# RB_Audio.net
KiCad netlist of a schematic drawn in Altium Designer
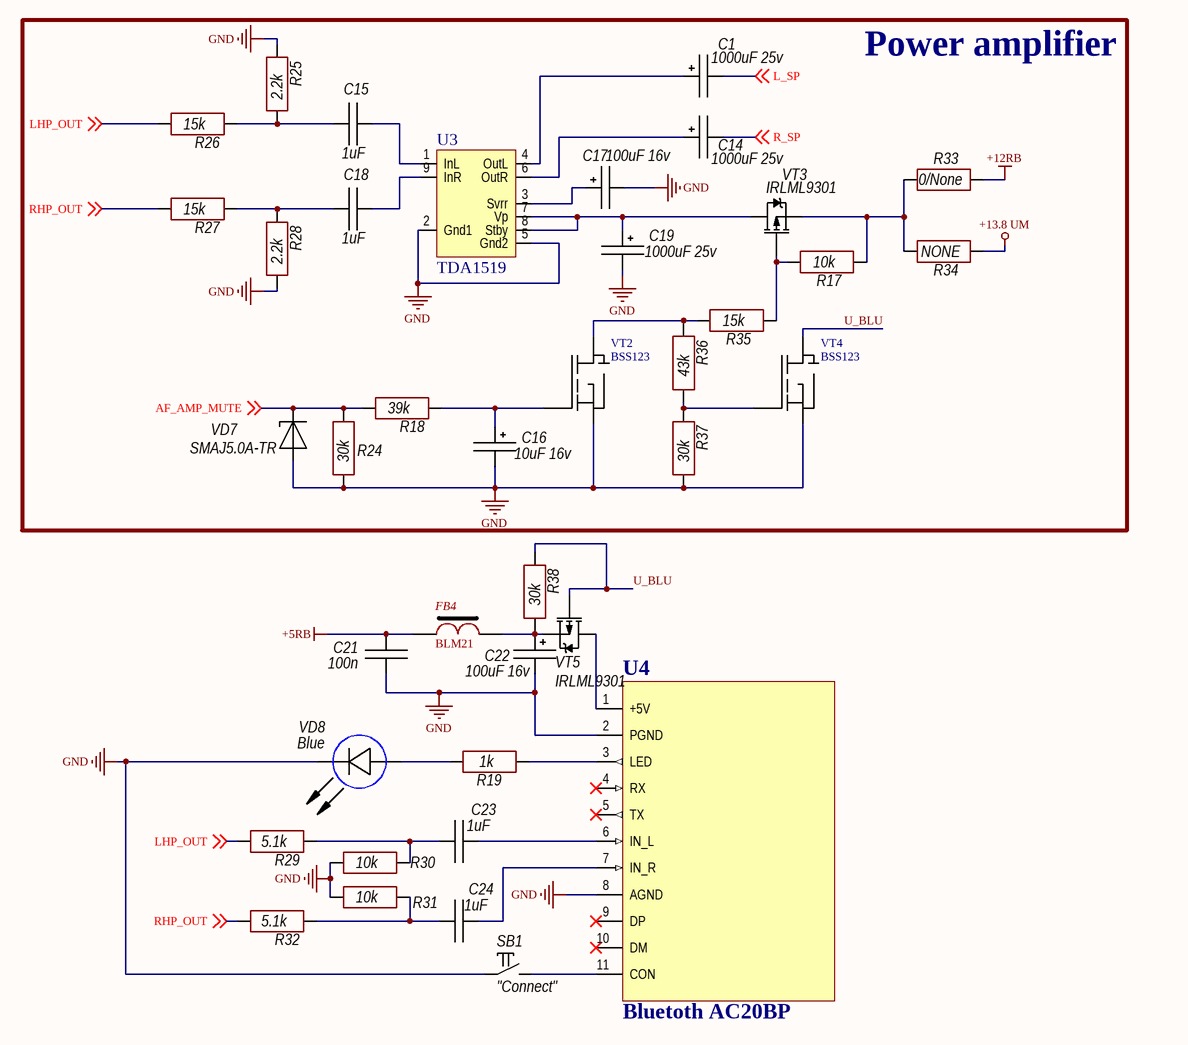
[diagram p0: RB_Audio.SchDoc]

(export (version "E")
  (design (tool "Eeschema 10.0.6"))
  (components
    (comp (ref "C1")
      (value "1000uF 25v")
      (footprint "standard:D10C5H12.5")
      (libsource (lib "Discrete") (part "AlumCap"))
    )
    (comp (ref "C14")
      (value "1000uF 25v")
      (footprint "standard:D10C5H12.5")
      (libsource (lib "") (part "AlumCap_1"))
    )
    (comp (ref "C15")
      (value "1uF")
      (footprint "standard:CH0805C")
      (libsource (lib "Discrete") (part "Capacitor"))
    )
    (comp (ref "C16")
      (value "10uF 16v")
      (footprint "standard:TANTAL_B")
      (libsource (lib "Discrete") (part "TantalCap"))
    )
    (comp (ref "C17")
      (value "100uF 16v")
      (footprint "standard:TANTAL_D")
      (libsource (lib "Discrete") (part "TantalCap"))
    )
    (comp (ref "C18")
      (value "1uF")
      (footprint "standard:CH0805C")
      (libsource (lib "Discrete") (part "Capacitor"))
    )
    (comp (ref "C19")
      (value "1000uF 25v")
      (footprint "standard:D10C5H12.5")
      (libsource (lib "Discrete") (part "AlumCap"))
    )
    (comp (ref "C21")
      (value "100n")
      (footprint "standard:CH0805C")
      (libsource (lib "Discrete") (part "Capacitor"))
    )
    (comp (ref "C22")
      (value "100uF 16v")
      (footprint "standard:D6.3C2.5H11")
      (libsource (lib "Discrete") (part "AlumCap"))
    )
    (comp (ref "C23")
      (value "1uF")
      (footprint "standard:CH0805C")
      (libsource (lib "Discrete") (part "Capacitor"))
    )
    (comp (ref "C24")
      (value "1uF")
      (footprint "standard:CH0805C")
      (libsource (lib "Discrete") (part "Capacitor"))
    )
    (comp (ref "FB4") (value "BLM21") (footprint "CH0805L") (libsource (lib "Discrete") (part "FB-1")))
    (comp (ref "R17") (value "10k") (footprint "standard:CH0805R") (libsource (lib "") (part "Resistor_1")))
    (comp (ref "R18") (value "39k") (footprint "standard:CH0805R") (libsource (lib "") (part "Resistor_1")))
    (comp (ref "R19") (value "1k") (footprint "standard:CH0805R") (libsource (lib "") (part "Resistor_1")))
    (comp (ref "R24")
      (value "30k")
      (footprint "standard:CH0805R")
      (libsource (lib "Discrete") (part "Resistor"))
    )
    (comp (ref "R25")
      (value "2.2k")
      (footprint "standard:CH0805R")
      (libsource (lib "Discrete") (part "Resistor"))
    )
    (comp (ref "R26") (value "15k") (footprint "standard:CH0805R") (libsource (lib "") (part "Resistor_1")))
    (comp (ref "R27") (value "15k") (footprint "standard:CH0805R") (libsource (lib "") (part "Resistor_1")))
    (comp (ref "R28") (value "2.2k") (footprint "standard:CH0805R") (libsource (lib "") (part "Resistor_2")))
    (comp (ref "R29") (value "5.1k") (footprint "standard:CH0805R") (libsource (lib "") (part "Resistor_1")))
    (comp (ref "R30") (value "10k") (footprint "standard:CH0805R") (libsource (lib "") (part "Resistor_1")))
    (comp (ref "R31") (value "10k") (footprint "standard:CH0805R") (libsource (lib "") (part "Resistor_1")))
    (comp (ref "R32") (value "5.1k") (footprint "standard:CH0805R") (libsource (lib "") (part "Resistor_1")))
    (comp (ref "R33")
      (value "0/None")
      (footprint "standard:CH1206R")
      (libsource (lib "") (part "Resistor_1"))
    )
    (comp (ref "R34") (value "NONE") (footprint "standard:CH1206R") (libsource (lib "") (part "Resistor_1")))
    (comp (ref "R35") (value "15k") (footprint "standard:CH0805R") (libsource (lib "") (part "Resistor_1")))
    (comp (ref "R36")
      (value "43k")
      (footprint "standard:CH0805R")
      (libsource (lib "Discrete") (part "Resistor"))
    )
    (comp (ref "R37")
      (value "30k")
      (footprint "standard:CH0805R")
      (libsource (lib "Discrete") (part "Resistor"))
    )
    (comp (ref "R38")
      (value "30k")
      (footprint "standard:CH0805R")
      (libsource (lib "Discrete") (part "Resistor"))
    )
    (comp (ref "SB1")
      (value "\"Connect\"")
      (footprint "custom:BUT: 6x6 mm (R)")
      (description "6x6 mm")
      (libsource (lib "Connectors") (part "Tactile switches"))
    )
    (comp (ref "U3") (value "TDA1519") (footprint "SOT110B") (libsource (lib "Discrete") (part "TDA1519")))
    (comp (ref "U4")
      (value "Bluetoth AC20BP")
      (footprint "Bluetooth 11PIN")
      (libsource (lib "Module") (part "Bluetoth AC20BP Module"))
    )
    (comp (ref "VD7")
      (value "SMAJ5.0A-TR")
      (footprint "standard:SMA")
      (libsource (lib "Diods") (part "Diod Zener"))
    )
    (comp (ref "VD8")
      (value "Blue")
      (footprint "standard:CH0805LB")
      (libsource (lib "Discrete") (part "LED"))
    )
    (comp (ref "VT2") (value "BSS123") (footprint "SOT23_132") (libsource (lib "Transistor") (part "BSS123")))
    (comp (ref "VT3")
      (value "IRLML9301")
      (footprint "standard:SOT23_132")
      (description "Mosfet")
      (libsource (lib "Transistor") (part "IRLML9301"))
    )
    (comp (ref "VT4") (value "BSS123") (footprint "SOT23_132") (libsource (lib "Transistor") (part "BSS123")))
    (comp (ref "VT5")
      (value "IRLML9301")
      (footprint "standard:SOT23_132")
      (description "Mosfet")
      (libsource (lib "") (part "IRLML9301_1"))
    )
  )
  (nets
    (net (code "1") (name "+5RB") (class "Default")
      (node (ref "C21") (pin "2") (pinfunction "2_2") (pintype "power_in"))
      (node (ref "FB4") (pin "2") (pinfunction "2_2") (pintype "passive"))
    )
    (net (code "2") (name "+12RB") (class "Default")
      (node (ref "R33") (pin "2") (pinfunction "2_2") (pintype "passive"))
    )
    (net (code "3") (name "+13.8 UM") (class "Default")
      (node (ref "R34") (pin "2") (pinfunction "2_2") (pintype "passive"))
    )
    (net (code "4") (name "/U_BLU") (class "Default")
      (node (ref "R38") (pin "2") (pinfunction "2_2") (pintype "passive"))
      (node (ref "VT4") (pin "3") (pinfunction "D_3") (pintype "passive"))
      (node (ref "VT5") (pin "1") (pinfunction "G_1") (pintype "passive"))
    )
    (net (code "5") (name "AF_AMP_MUTE") (class "Default")
      (node (ref "R18") (pin "1") (pinfunction "1_1") (pintype "passive"))
      (node (ref "R24") (pin "2") (pinfunction "2_2") (pintype "passive"))
      (node (ref "VD7") (pin "2") (pinfunction "C_2") (pintype "passive"))
    )
    (net (code "6") (name "GND") (class "Default")
      (node (ref "C16") (pin "2") (pinfunction "2_2") (pintype "power_in"))
      (node (ref "C17") (pin "2") (pinfunction "2_2") (pintype "power_in"))
      (node (ref "C19") (pin "2") (pinfunction "2_2") (pintype "power_in"))
      (node (ref "C21") (pin "1") (pinfunction "1_1") (pintype "power_in"))
      (node (ref "C22") (pin "2") (pinfunction "2_2") (pintype "power_in"))
      (node (ref "R24") (pin "1") (pinfunction "1_1") (pintype "passive"))
      (node (ref "R25") (pin "2") (pinfunction "2_2") (pintype "passive"))
      (node (ref "R28") (pin "1") (pinfunction "1_1") (pintype "passive"))
      (node (ref "R30") (pin "1") (pinfunction "1_1") (pintype "passive"))
      (node (ref "R31") (pin "1") (pinfunction "1_1") (pintype "passive"))
      (node (ref "R37") (pin "1") (pinfunction "1_1") (pintype "passive"))
      (node (ref "SB1") (pin "1") (pinfunction "1_1") (pintype "passive"))
      (node (ref "U3") (pin "2") (pinfunction "Gnd1_2") (pintype "passive"))
      (node (ref "U3") (pin "5") (pinfunction "Gnd2_5") (pintype "passive"))
      (node (ref "U4") (pin "2") (pinfunction "PGND_2") (pintype "passive"))
      (node (ref "U4") (pin "8") (pinfunction "AGND_8") (pintype "passive"))
      (node (ref "VD7") (pin "1") (pinfunction "A_1") (pintype "passive"))
      (node (ref "VD8") (pin "2") (pinfunction "C_2") (pintype "passive"))
      (node (ref "VT2") (pin "2") (pinfunction "S_2") (pintype "passive"))
      (node (ref "VT4") (pin "2") (pinfunction "S_2") (pintype "passive"))
    )
    (net (code "7") (name "LHP_OUT") (class "Default")
      (node (ref "R26") (pin "1") (pinfunction "1_1") (pintype "passive"))
      (node (ref "R29") (pin "1") (pinfunction "1_1") (pintype "passive"))
    )
    (net (code "8") (name "L_SP") (class "Default")
      (node (ref "C1") (pin "2") (pinfunction "2_2") (pintype "power_in"))
    )
    (net (code "9") (name "Net-(C15-Pad1)") (class "Default")
      (node (ref "C15") (pin "1") (pinfunction "1_1") (pintype "power_in"))
      (node (ref "R25") (pin "1") (pinfunction "1_1") (pintype "passive"))
      (node (ref "R26") (pin "2") (pinfunction "2_2") (pintype "passive"))
    )
    (net (code "10") (name "Net-(C18-Pad1)") (class "Default")
      (node (ref "C18") (pin "1") (pinfunction "1_1") (pintype "power_in"))
      (node (ref "R27") (pin "2") (pinfunction "2_2") (pintype "passive"))
      (node (ref "R28") (pin "2") (pinfunction "2_2") (pintype "passive"))
    )
    (net (code "11") (name "Net-(C23-Pad1)") (class "Default")
      (node (ref "C23") (pin "1") (pinfunction "1_1") (pintype "power_in"))
      (node (ref "R29") (pin "2") (pinfunction "2_2") (pintype "passive"))
      (node (ref "R30") (pin "2") (pinfunction "2_2") (pintype "passive"))
    )
    (net (code "12") (name "Net-(C24-Pad1)") (class "Default")
      (node (ref "C24") (pin "1") (pinfunction "1_1") (pintype "power_in"))
      (node (ref "R31") (pin "2") (pinfunction "2_2") (pintype "passive"))
      (node (ref "R32") (pin "2") (pinfunction "2_2") (pintype "passive"))
    )
    (net (code "13") (name "Net-(U3-InL)") (class "Default")
      (node (ref "C15") (pin "2") (pinfunction "2_2") (pintype "power_in"))
      (node (ref "U3") (pin "1") (pinfunction "InL_1") (pintype "passive"))
    )
    (net (code "14") (name "Net-(U3-InR)") (class "Default")
      (node (ref "C18") (pin "2") (pinfunction "2_2") (pintype "power_in"))
      (node (ref "U3") (pin "9") (pinfunction "InR_9") (pintype "passive"))
    )
    (net (code "15") (name "Net-(U3-OutL)") (class "Default")
      (node (ref "C1") (pin "1") (pinfunction "1_1") (pintype "power_in"))
      (node (ref "U3") (pin "4") (pinfunction "OutL_4") (pintype "passive"))
    )
    (net (code "16") (name "Net-(U3-OutR)") (class "Default")
      (node (ref "C14") (pin "1") (pinfunction "1_1") (pintype "power_in"))
      (node (ref "U3") (pin "6") (pinfunction "OutR_6") (pintype "passive"))
    )
    (net (code "17") (name "Net-(U3-Stby)") (class "Default")
      (node (ref "C19") (pin "1") (pinfunction "1_1") (pintype "power_in"))
      (node (ref "U3") (pin "7") (pinfunction "Vp_7") (pintype "passive"))
      (node (ref "U3") (pin "8") (pinfunction "Stby_8") (pintype "passive"))
      (node (ref "VT3") (pin "3") (pinfunction "D_3") (pintype "passive"))
    )
    (net (code "18") (name "Net-(U3-Svrr)") (class "Default")
      (node (ref "C17") (pin "1") (pinfunction "1_1") (pintype "power_in"))
      (node (ref "U3") (pin "3") (pinfunction "Svrr_3") (pintype "passive"))
    )
    (net (code "19") (name "Net-(U4-+5V)") (class "Default")
      (node (ref "U4") (pin "1") (pinfunction "+5V_1") (pintype "power_in"))
      (node (ref "VT5") (pin "3") (pinfunction "D_3") (pintype "passive"))
    )
    (net (code "20") (name "Net-(U4-CON)") (class "Default")
      (node (ref "SB1") (pin "2") (pinfunction "2_2") (pintype "passive"))
      (node (ref "U4") (pin "11") (pinfunction "CON_11") (pintype "passive"))
    )
    (net (code "21") (name "Net-(U4-IN_L)") (class "Default")
      (node (ref "C23") (pin "2") (pinfunction "2_2") (pintype "power_in"))
      (node (ref "U4") (pin "6") (pinfunction "IN_L_6") (pintype "input"))
    )
    (net (code "22") (name "Net-(U4-IN_R)") (class "Default")
      (node (ref "C24") (pin "2") (pinfunction "2_2") (pintype "power_in"))
      (node (ref "U4") (pin "7") (pinfunction "IN_R_7") (pintype "input"))
    )
    (net (code "23") (name "Net-(U4-LED)") (class "Default")
      (node (ref "R19") (pin "2") (pinfunction "2_2") (pintype "passive"))
      (node (ref "U4") (pin "3") (pinfunction "LED_3") (pintype "output"))
    )
    (net (code "24") (name "Net-(VD8-A)") (class "Default")
      (node (ref "R19") (pin "1") (pinfunction "1_1") (pintype "passive"))
      (node (ref "VD8") (pin "1") (pinfunction "A_1") (pintype "passive"))
    )
    (net (code "25") (name "Net-(VT2-D)") (class "Default")
      (node (ref "R35") (pin "1") (pinfunction "1_1") (pintype "passive"))
      (node (ref "R36") (pin "2") (pinfunction "2_2") (pintype "passive"))
      (node (ref "VT2") (pin "3") (pinfunction "D_3") (pintype "passive"))
    )
    (net (code "26") (name "Net-(VT2-G)") (class "Default")
      (node (ref "C16") (pin "1") (pinfunction "1_1") (pintype "power_in"))
      (node (ref "R18") (pin "2") (pinfunction "2_2") (pintype "passive"))
      (node (ref "VT2") (pin "1") (pinfunction "G_1") (pintype "passive"))
    )
    (net (code "27") (name "Net-(VT3-G)") (class "Default")
      (node (ref "R17") (pin "1") (pinfunction "1_1") (pintype "passive"))
      (node (ref "R35") (pin "2") (pinfunction "2_2") (pintype "passive"))
      (node (ref "VT3") (pin "1") (pinfunction "G_1") (pintype "passive"))
    )
    (net (code "28") (name "Net-(VT3-S)") (class "Default")
      (node (ref "R17") (pin "2") (pinfunction "2_2") (pintype "passive"))
      (node (ref "R33") (pin "1") (pinfunction "1_1") (pintype "passive"))
      (node (ref "R34") (pin "1") (pinfunction "1_1") (pintype "passive"))
      (node (ref "VT3") (pin "2") (pinfunction "S_2") (pintype "passive"))
    )
    (net (code "29") (name "Net-(VT4-G)") (class "Default")
      (node (ref "R36") (pin "1") (pinfunction "1_1") (pintype "passive"))
      (node (ref "R37") (pin "2") (pinfunction "2_2") (pintype "passive"))
      (node (ref "VT4") (pin "1") (pinfunction "G_1") (pintype "passive"))
    )
    (net (code "30") (name "Net-(VT5-S)") (class "Default")
      (node (ref "C22") (pin "1") (pinfunction "1_1") (pintype "power_in"))
      (node (ref "FB4") (pin "1") (pinfunction "1_1") (pintype "passive"))
      (node (ref "VT5") (pin "2") (pinfunction "S_2") (pintype "passive"))
    )
    (net (code "31") (name "RHP_OUT") (class "Default")
      (node (ref "R27") (pin "1") (pinfunction "1_1") (pintype "passive"))
      (node (ref "R32") (pin "1") (pinfunction "1_1") (pintype "passive"))
    )
    (net (code "32") (name "R_SP") (class "Default")
      (node (ref "C14") (pin "2") (pinfunction "2_2") (pintype "power_in"))
    )
    (net (code "33") (name "unconnected-(R38-Pad1)") (class "Default")
      (node (ref "R38") (pin "1") (pinfunction "1_1") (pintype "passive"))
    )
    (net (code "34") (name "unconnected-(U4-DM-Pad10)") (class "Default")
      (node (ref "U4") (pin "10") (pinfunction "DM_10") (pintype "passive+no_connect"))
    )
    (net (code "35") (name "unconnected-(U4-DP-Pad9)") (class "Default")
      (node (ref "U4") (pin "9") (pinfunction "DP_9") (pintype "passive+no_connect"))
    )
    (net (code "36") (name "unconnected-(U4-RX-Pad4)") (class "Default")
      (node (ref "U4") (pin "4") (pinfunction "RX_4") (pintype "input+no_connect"))
    )
    (net (code "37") (name "unconnected-(U4-TX-Pad5)") (class "Default")
      (node (ref "U4") (pin "5") (pinfunction "TX_5") (pintype "output+no_connect"))
    )
  )
)
